# SCH_SHUBH_NFC_CARD_2025-03-09.net
KiCad netlist of a schematic drawn in EasyEDA
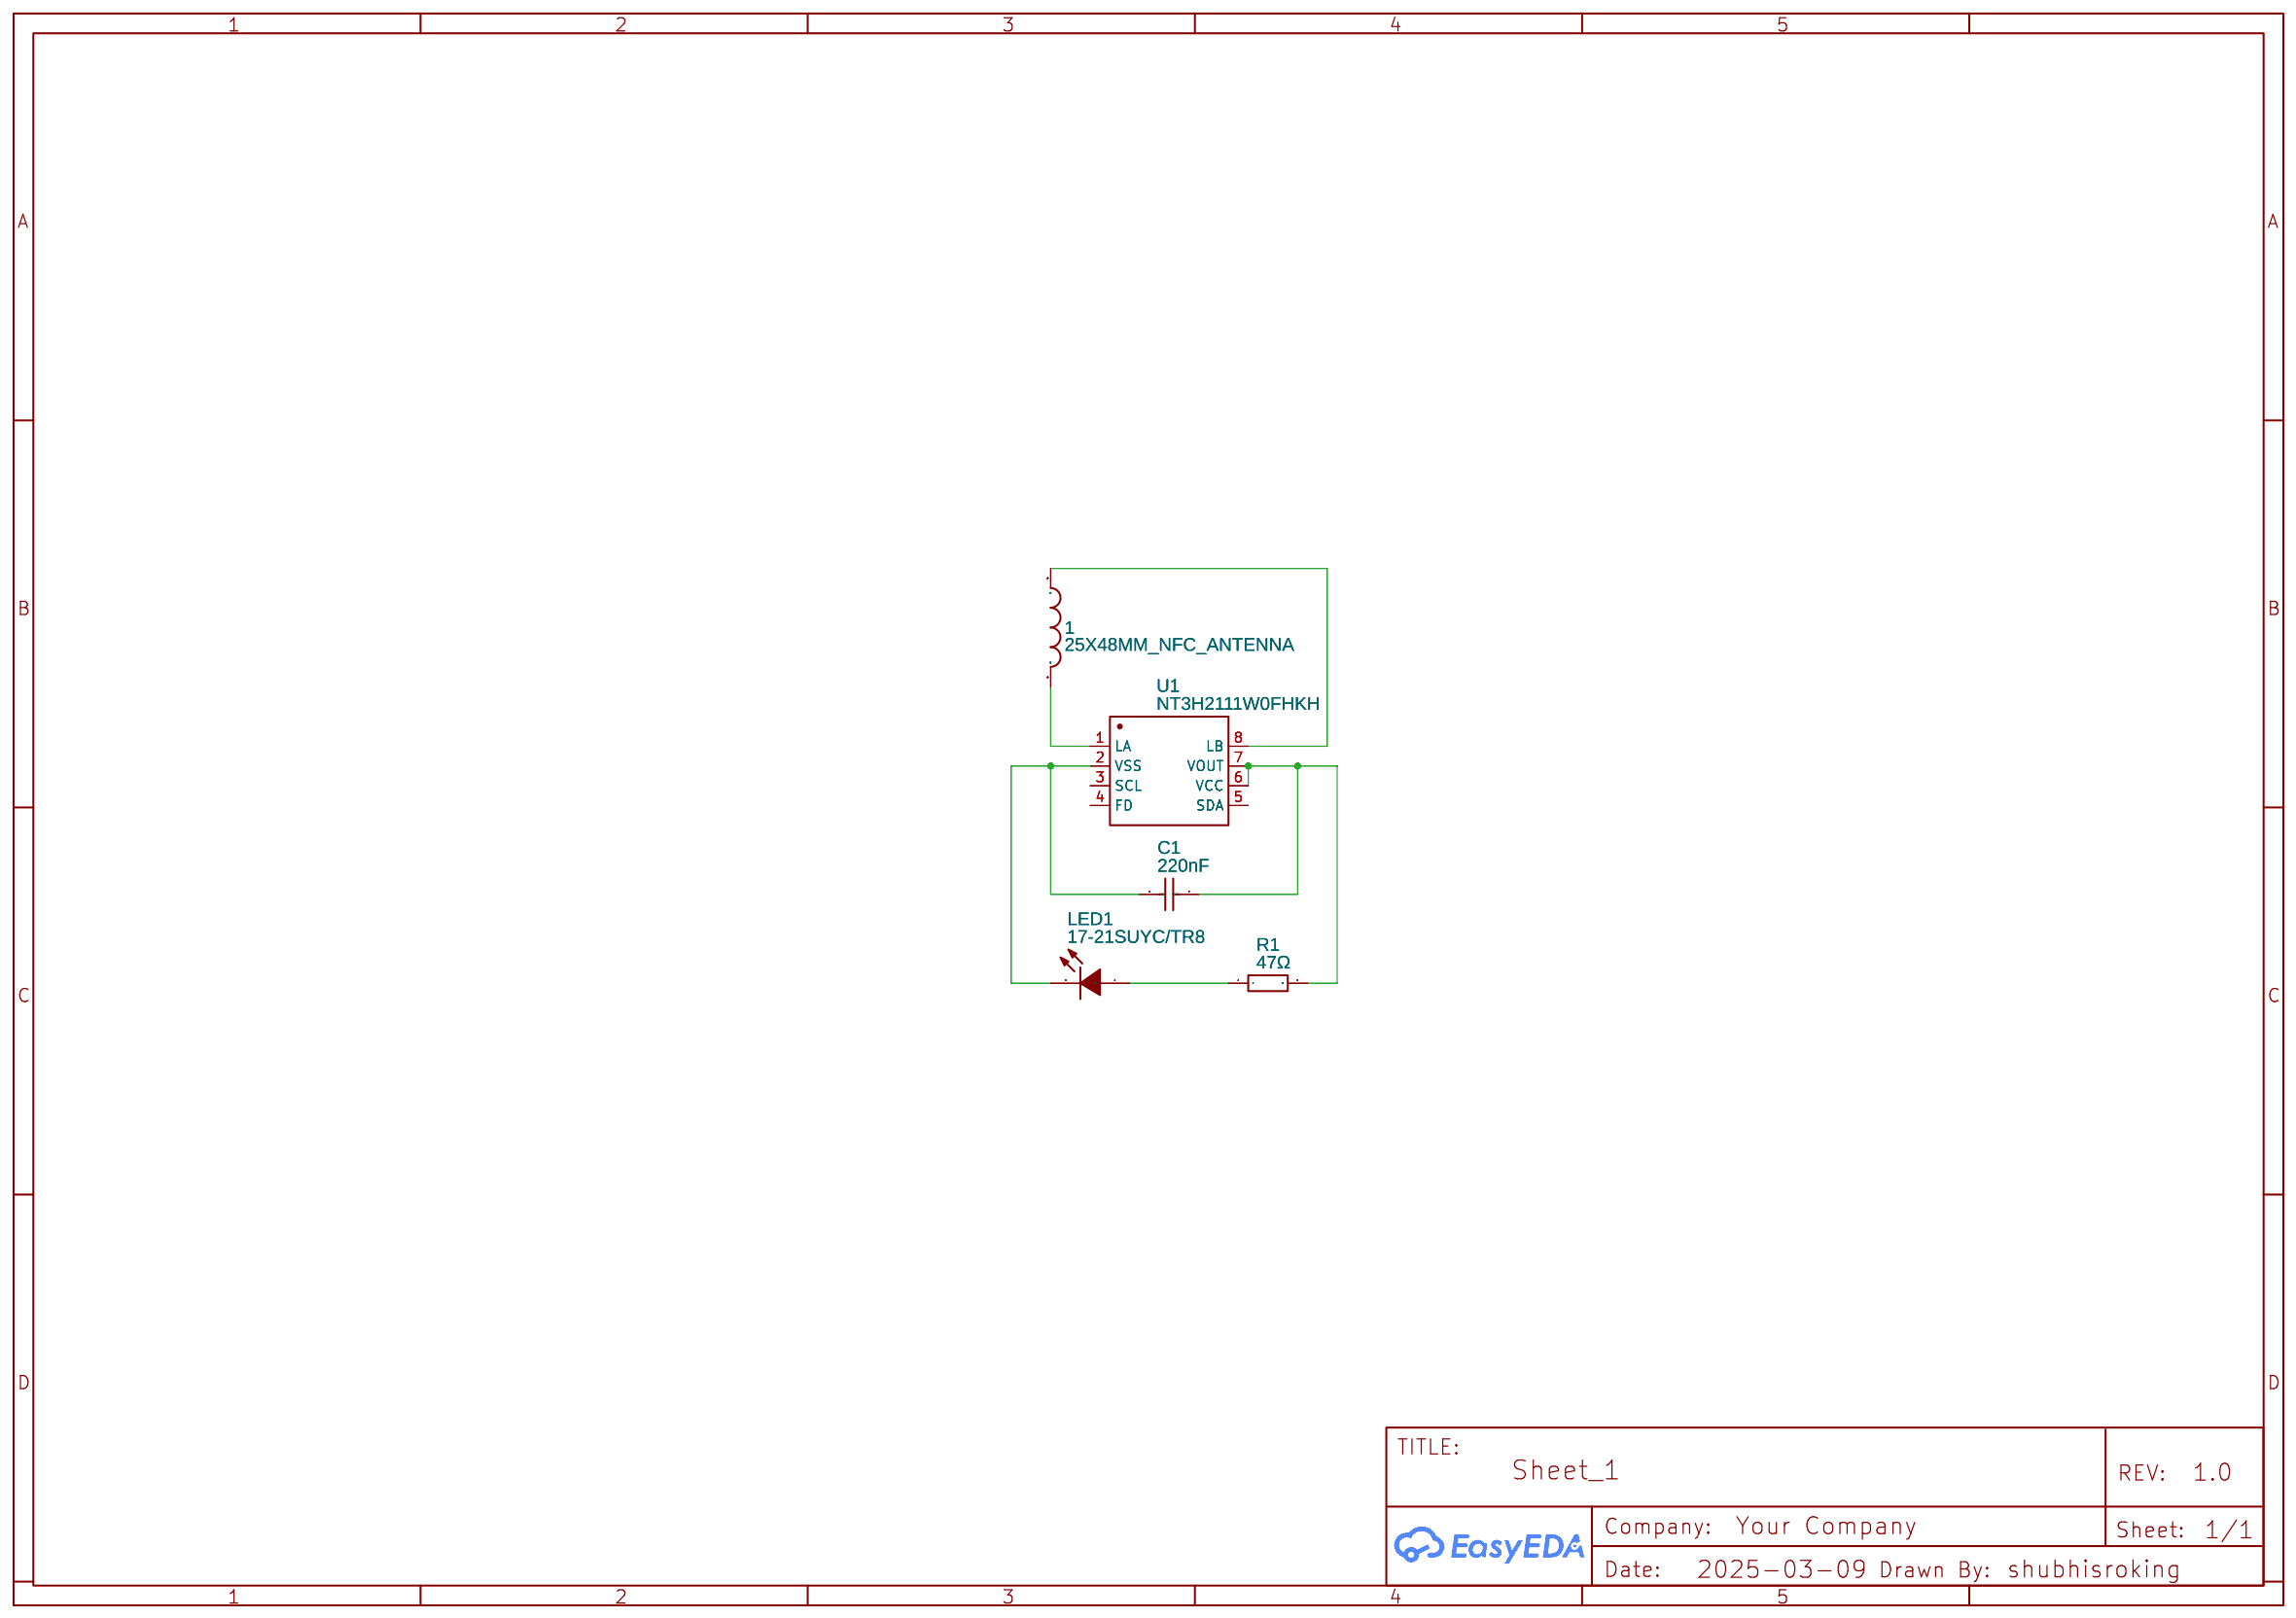
[diagram p0: schematic sheet]

(export (version "E")
  (design (tool "Eeschema 10.0.6"))
  (components
    (comp (ref "1") (value "25X48MM_NFC_ANTENNA") (libsource (lib "") (part "25X48MM_NFC_ANTENNA")))
    (comp (ref "C1")
      (value "220nF")
      (fields
        (field (name "Manufacturer Part") "CL10B224KA8NNNC")
        (field (name "Manufacturer") "SAMSUNG(三星)")
      )
      (libsource (lib "") (part "CL10B224KA8NNNC"))
    )
    (comp (ref "LED1")
      (value "17-21SUYC/TR8")
      (fields (field (name "Manufacturer Part") "KT-0805黄灯") (field (name "Manufacturer") "KENTO"))
      (libsource (lib "") (part "17-21SUYC/TR8"))
    )
    (comp (ref "R1")
      (value "47Ω")
      (fields
        (field (name "Manufacturer Part") "0603WAF470JT5E")
        (field (name "Manufacturer") "UNI-ROYAL(厚声)")
      )
      (libsource (lib "") (part "0603WAF470JT5E"))
    )
    (comp (ref "U1")
      (value "NT3H2111W0FHKH")
      (fields (field (name "Manufacturer") "NXP(恩智浦)"))
      (libsource (lib "") (part "NT3H2111W0FHKH"))
    )
  )
  (nets
    (net (code "1") (name "Net-(LED1-+)") (class "Default")
      (node (ref "LED1") (pin "1") (pinfunction "+_1") (pintype "unspecified"))
      (node (ref "R1") (pin "1") (pinfunction "1_1") (pintype "input"))
    )
    (net (code "2") (name "Net-(LED1--)") (class "Default")
      (node (ref "C1") (pin "1") (pinfunction "1_1") (pintype "input"))
      (node (ref "LED1") (pin "2") (pinfunction "-_2") (pintype "unspecified"))
      (node (ref "U1") (pin "2") (pinfunction "VSS_2") (pintype "unspecified"))
    )
    (net (code "3") (name "Net-(U1-LA)") (class "Default")
      (node (ref "1") (pin "P$2") (pinfunction "P$2_P$2") (pintype "bidirectional"))
      (node (ref "U1") (pin "1") (pinfunction "LA_1") (pintype "unspecified"))
    )
    (net (code "4") (name "Net-(U1-LB)") (class "Default")
      (node (ref "1") (pin "P$1") (pinfunction "P$1_P$1") (pintype "bidirectional"))
      (node (ref "U1") (pin "8") (pinfunction "LB_8") (pintype "unspecified"))
    )
    (net (code "5") (name "Net-(U1-VCC)") (class "Default")
      (node (ref "C1") (pin "2") (pinfunction "2_2") (pintype "input"))
      (node (ref "R1") (pin "2") (pinfunction "2_2") (pintype "input"))
      (node (ref "U1") (pin "6") (pinfunction "VCC_6") (pintype "unspecified"))
      (node (ref "U1") (pin "7") (pinfunction "VOUT_7") (pintype "unspecified"))
    )
    (net (code "6") (name "unconnected-(U1-FD-Pad4)") (class "Default")
      (node (ref "U1") (pin "4") (pinfunction "FD_4") (pintype "unspecified"))
    )
    (net (code "7") (name "unconnected-(U1-SCL-Pad3)") (class "Default")
      (node (ref "U1") (pin "3") (pinfunction "SCL_3") (pintype "unspecified"))
    )
    (net (code "8") (name "unconnected-(U1-SDA-Pad5)") (class "Default")
      (node (ref "U1") (pin "5") (pinfunction "SDA_5") (pintype "unspecified"))
    )
  )
)
